# LPRD_Sensors_1_4.net
KiCad netlist of a schematic drawn in EAGLE
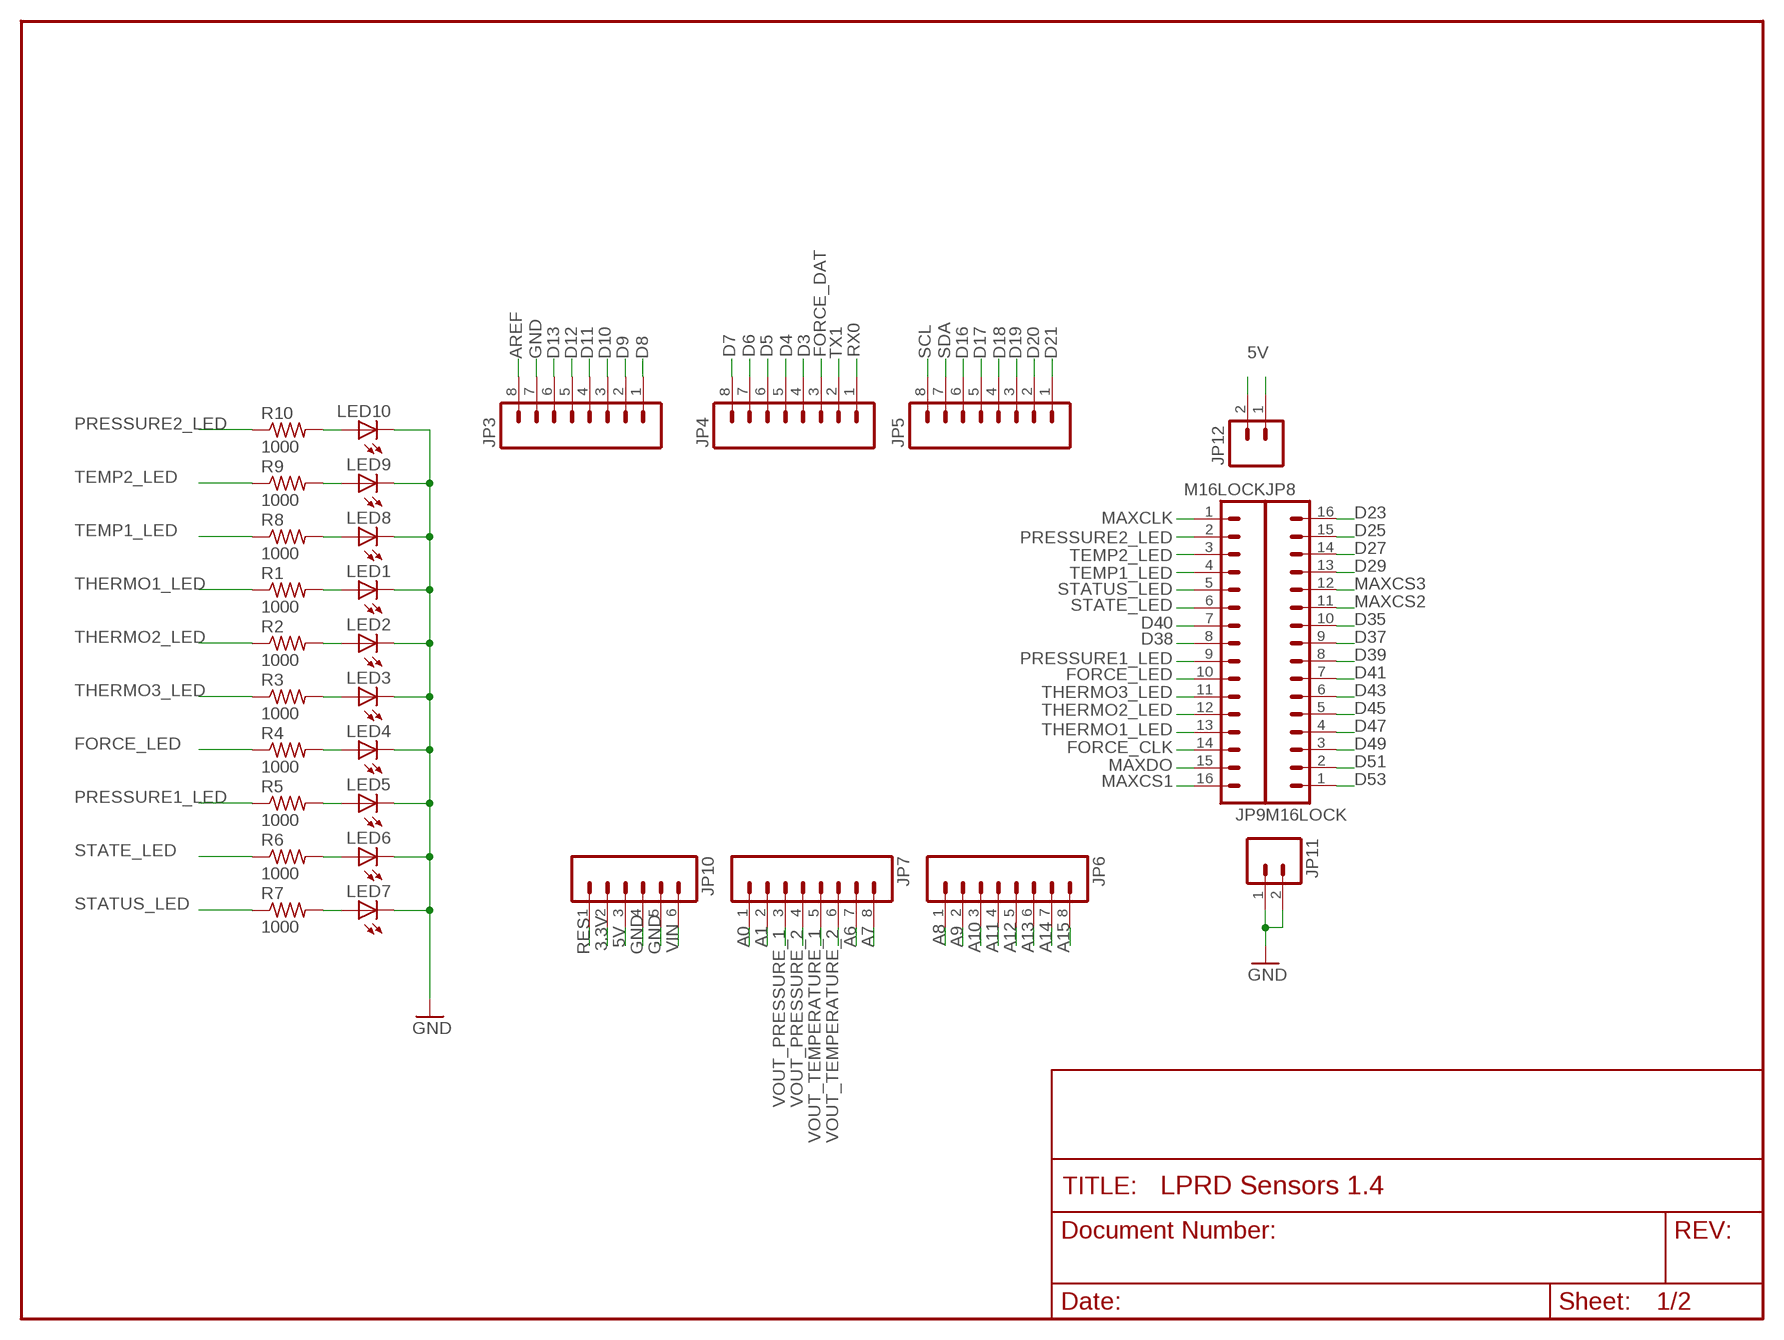
[diagram p0: schematic, sheet 1]
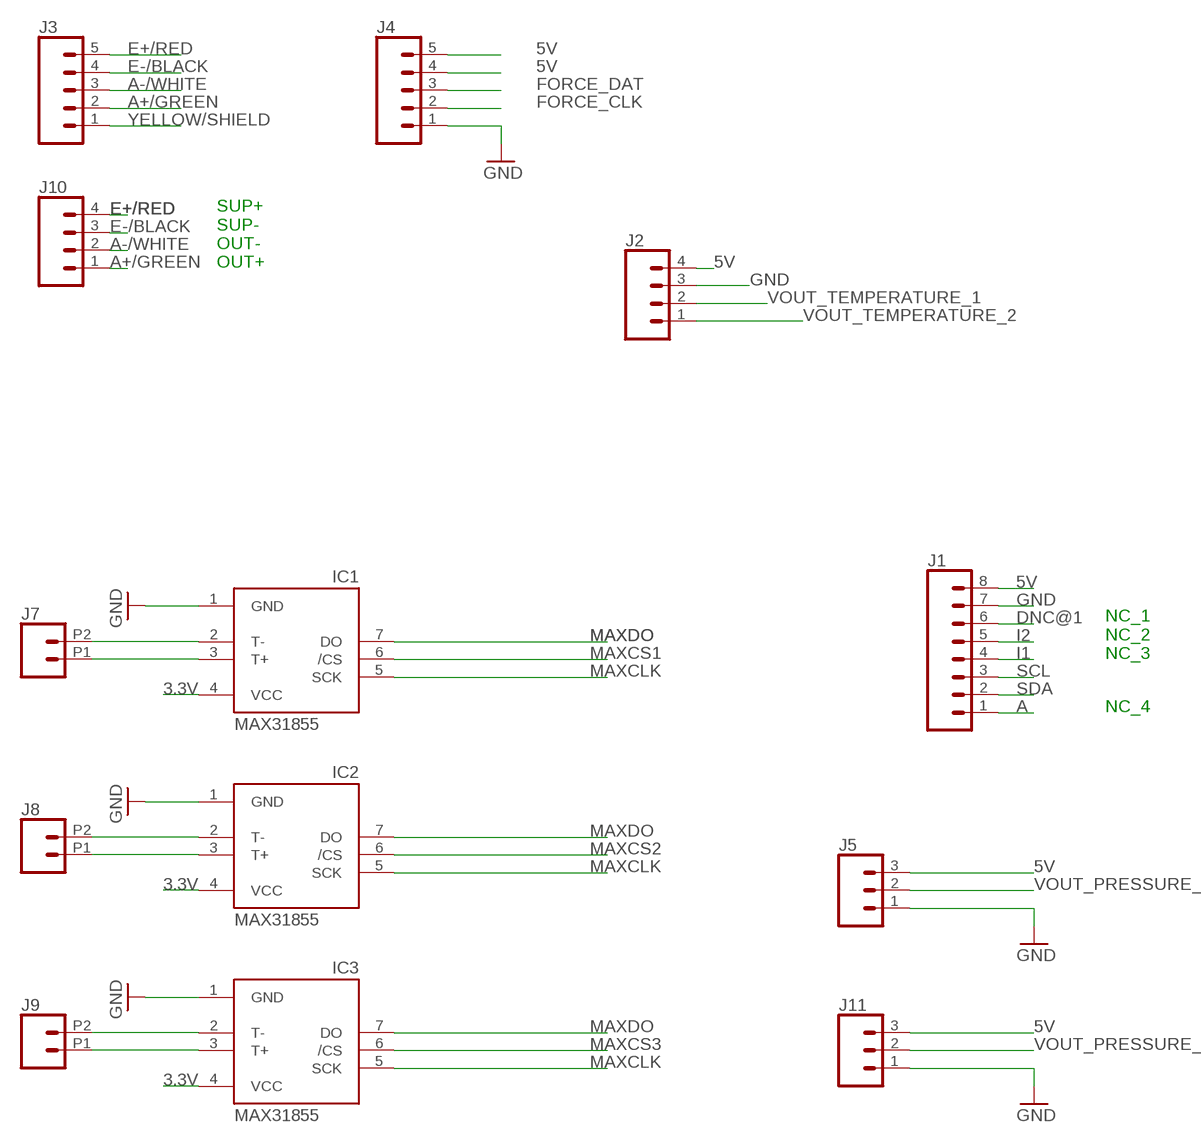
[diagram p1: schematic, sheet 2]

(export (version "E")
  (design (tool "Eeschema 10.0.6"))
  (components
    (comp (ref "IC1")
      (value "MAX31855")
      (footprint "eagle-import:SO08")
      (libsource (lib "eagle-import") (part "MAX6675"))
    )
    (comp (ref "IC2")
      (value "MAX31855")
      (footprint "eagle-import:SO08")
      (libsource (lib "eagle-import") (part "MAX6675"))
    )
    (comp (ref "IC3")
      (value "MAX31855")
      (footprint "eagle-import:SO08")
      (libsource (lib "eagle-import") (part "MAX6675"))
    )
    (comp (ref "J1")
      (value "CONN_08\"")
      (footprint "eagle-import:1X08")
      (libsource (lib "eagle-import") (part "CONN_08{dblquote}"))
    )
    (comp (ref "J2")
      (value "CONN_04")
      (footprint "eagle-import:1X04")
      (libsource (lib "eagle-import") (part "CONN_04"))
    )
    (comp (ref "J3")
      (value "CONN_05")
      (footprint "eagle-import:1X05")
      (libsource (lib "eagle-import") (part "CONN_05"))
    )
    (comp (ref "J4")
      (value "CONN_05")
      (footprint "eagle-import:1X05")
      (libsource (lib "eagle-import") (part "CONN_05"))
    )
    (comp (ref "J5")
      (value "CONN_03-SCREW-5MM")
      (footprint "eagle-import:SCREWTERMINAL-5MM-3")
      (libsource (lib "eagle-import") (part "CONN_03-SCREW-5MM"))
    )
    (comp (ref "J7")
      (value "CONN_022.54MM_SCREWTERM")
      (footprint "eagle-import:1X02_2.54_SCREWTERM")
      (libsource (lib "eagle-import") (part "CONN_022.54MM_SCREWTERM"))
    )
    (comp (ref "J8")
      (value "CONN_022.54MM_SCREWTERM")
      (footprint "eagle-import:1X02_2.54_SCREWTERM")
      (libsource (lib "eagle-import") (part "CONN_022.54MM_SCREWTERM"))
    )
    (comp (ref "J9")
      (value "CONN_022.54MM_SCREWTERM")
      (footprint "eagle-import:1X02_2.54_SCREWTERM")
      (libsource (lib "eagle-import") (part "CONN_022.54MM_SCREWTERM"))
    )
    (comp (ref "J10")
      (value "CONN_04SCREW")
      (footprint "eagle-import:SCREWTERMINAL-3.5MM-4")
      (libsource (lib "eagle-import") (part "CONN_04SCREW"))
    )
    (comp (ref "J11")
      (value "CONN_03-SCREW-5MM")
      (footprint "eagle-import:SCREWTERMINAL-5MM-3")
      (libsource (lib "eagle-import") (part "CONN_03-SCREW-5MM"))
    )
    (comp (ref "JP3")
      (value "M08LOCK")
      (footprint "eagle-import:1X08_LOCK")
      (libsource (lib "eagle-import") (part "M08LOCK"))
    )
    (comp (ref "JP4")
      (value "M08LOCK")
      (footprint "eagle-import:1X08_LOCK")
      (libsource (lib "eagle-import") (part "M08LOCK"))
    )
    (comp (ref "JP5")
      (value "M08LOCK")
      (footprint "eagle-import:1X08_LOCK")
      (libsource (lib "eagle-import") (part "M08LOCK"))
    )
    (comp (ref "JP6")
      (value "M08LOCK")
      (footprint "eagle-import:1X08_LOCK")
      (libsource (lib "eagle-import") (part "M08LOCK"))
    )
    (comp (ref "JP7")
      (value "M08LOCK")
      (footprint "eagle-import:1X08_LOCK")
      (libsource (lib "eagle-import") (part "M08LOCK"))
    )
    (comp (ref "JP8")
      (value "M16LOCK")
      (footprint "eagle-import:1X16_LOCK")
      (libsource (lib "eagle-import") (part "M16LOCK"))
    )
    (comp (ref "JP9")
      (value "M16LOCK")
      (footprint "eagle-import:1X16_LOCK")
      (libsource (lib "eagle-import") (part "M16LOCK"))
    )
    (comp (ref "JP10")
      (value "M06LOCK")
      (footprint "eagle-import:1X06_LOCK")
      (libsource (lib "eagle-import") (part "M06LOCK"))
    )
    (comp (ref "JP11")
      (value "M02LOCK")
      (footprint "eagle-import:1X02_LOCK")
      (libsource (lib "eagle-import") (part "M02LOCK"))
    )
    (comp (ref "JP12")
      (value "M02LOCK")
      (footprint "eagle-import:1X02_LOCK")
      (libsource (lib "eagle-import") (part "M02LOCK"))
    )
    (comp (ref "LED1")
      (value "LEDCHIP-LED0805")
      (footprint "eagle-import:CHIP-LED0805")
      (libsource (lib "eagle-import") (part "LEDCHIP-LED0805"))
    )
    (comp (ref "LED2")
      (value "LEDCHIP-LED0805")
      (footprint "eagle-import:CHIP-LED0805")
      (libsource (lib "eagle-import") (part "LEDCHIP-LED0805"))
    )
    (comp (ref "LED3")
      (value "LEDCHIP-LED0805")
      (footprint "eagle-import:CHIP-LED0805")
      (libsource (lib "eagle-import") (part "LEDCHIP-LED0805"))
    )
    (comp (ref "LED4")
      (value "LEDCHIP-LED0805")
      (footprint "eagle-import:CHIP-LED0805")
      (libsource (lib "eagle-import") (part "LEDCHIP-LED0805"))
    )
    (comp (ref "LED5")
      (value "LEDCHIP-LED0805")
      (footprint "eagle-import:CHIP-LED0805")
      (libsource (lib "eagle-import") (part "LEDCHIP-LED0805"))
    )
    (comp (ref "LED6")
      (value "LEDCHIP-LED0805")
      (footprint "eagle-import:CHIP-LED0805")
      (libsource (lib "eagle-import") (part "LEDCHIP-LED0805"))
    )
    (comp (ref "LED7")
      (value "LEDCHIP-LED0805")
      (footprint "eagle-import:CHIP-LED0805")
      (libsource (lib "eagle-import") (part "LEDCHIP-LED0805"))
    )
    (comp (ref "LED8")
      (value "LEDCHIP-LED0805")
      (footprint "eagle-import:CHIP-LED0805")
      (libsource (lib "eagle-import") (part "LEDCHIP-LED0805"))
    )
    (comp (ref "LED9")
      (value "LEDCHIP-LED0805")
      (footprint "eagle-import:CHIP-LED0805")
      (libsource (lib "eagle-import") (part "LEDCHIP-LED0805"))
    )
    (comp (ref "LED10")
      (value "LEDCHIP-LED0805")
      (footprint "eagle-import:CHIP-LED0805")
      (libsource (lib "eagle-import") (part "LEDCHIP-LED0805"))
    )
    (comp (ref "R1")
      (value "1000")
      (footprint "eagle-import:R0805")
      (libsource (lib "eagle-import") (part "R-US_R0805"))
    )
    (comp (ref "R2")
      (value "1000")
      (footprint "eagle-import:R0805")
      (libsource (lib "eagle-import") (part "R-US_R0805"))
    )
    (comp (ref "R3")
      (value "1000")
      (footprint "eagle-import:R0805")
      (libsource (lib "eagle-import") (part "R-US_R0805"))
    )
    (comp (ref "R4")
      (value "1000")
      (footprint "eagle-import:R0805")
      (libsource (lib "eagle-import") (part "R-US_R0805"))
    )
    (comp (ref "R5")
      (value "1000")
      (footprint "eagle-import:R0805")
      (libsource (lib "eagle-import") (part "R-US_R0805"))
    )
    (comp (ref "R6")
      (value "1000")
      (footprint "eagle-import:R0805")
      (libsource (lib "eagle-import") (part "R-US_R0805"))
    )
    (comp (ref "R7")
      (value "1000")
      (footprint "eagle-import:R0805")
      (libsource (lib "eagle-import") (part "R-US_R0805"))
    )
    (comp (ref "R8")
      (value "1000")
      (footprint "eagle-import:R0805")
      (libsource (lib "eagle-import") (part "R-US_R0805"))
    )
    (comp (ref "R9")
      (value "1000")
      (footprint "eagle-import:R0805")
      (libsource (lib "eagle-import") (part "R-US_R0805"))
    )
    (comp (ref "R10")
      (value "1000")
      (footprint "eagle-import:R0805")
      (libsource (lib "eagle-import") (part "R-US_R0805"))
    )
  )
  (nets
    (net (code "1") (name "3.3V") (class "Default")
      (node (ref "IC1") (pin "4") (pinfunction "VCC_4") (pintype "power_in"))
      (node (ref "IC2") (pin "4") (pinfunction "VCC_4") (pintype "power_in"))
      (node (ref "IC3") (pin "4") (pinfunction "VCC_4") (pintype "power_in"))
      (node (ref "JP10") (pin "2") (pinfunction "2_2") (pintype "passive"))
    )
    (net (code "2") (name "5V") (class "Default")
      (node (ref "J1") (pin "8") (pinfunction "8_8") (pintype "passive"))
      (node (ref "J11") (pin "3") (pinfunction "3_3") (pintype "passive"))
      (node (ref "J2") (pin "4") (pinfunction "4_4") (pintype "passive"))
      (node (ref "J4") (pin "4") (pinfunction "4_4") (pintype "passive"))
      (node (ref "J4") (pin "5") (pinfunction "5_5") (pintype "passive"))
      (node (ref "J5") (pin "3") (pinfunction "3_3") (pintype "passive"))
      (node (ref "JP10") (pin "3") (pinfunction "3_3") (pintype "passive"))
      (node (ref "JP12") (pin "1") (pinfunction "1_1") (pintype "passive"))
      (node (ref "JP12") (pin "2") (pinfunction "2_2") (pintype "passive"))
    )
    (net (code "3") (name "A") (class "Default")
      (node (ref "J1") (pin "1") (pinfunction "1_1") (pintype "passive"))
    )
    (net (code "4") (name "A+{slash}GREEN") (class "Default")
      (node (ref "J10") (pin "1") (pinfunction "1_1") (pintype "passive"))
      (node (ref "J3") (pin "2") (pinfunction "2_2") (pintype "passive"))
    )
    (net (code "5") (name "A-{slash}WHITE") (class "Default")
      (node (ref "J10") (pin "2") (pinfunction "2_2") (pintype "passive"))
      (node (ref "J3") (pin "3") (pinfunction "3_3") (pintype "passive"))
    )
    (net (code "6") (name "A0") (class "Default")
      (node (ref "JP7") (pin "1") (pinfunction "1_1") (pintype "passive"))
    )
    (net (code "7") (name "A1") (class "Default")
      (node (ref "JP7") (pin "2") (pinfunction "2_2") (pintype "passive"))
    )
    (net (code "8") (name "A6") (class "Default")
      (node (ref "JP7") (pin "7") (pinfunction "7_7") (pintype "passive"))
    )
    (net (code "9") (name "A7") (class "Default")
      (node (ref "JP7") (pin "8") (pinfunction "8_8") (pintype "passive"))
    )
    (net (code "10") (name "A8") (class "Default")
      (node (ref "JP6") (pin "1") (pinfunction "1_1") (pintype "passive"))
    )
    (net (code "11") (name "A9") (class "Default")
      (node (ref "JP6") (pin "2") (pinfunction "2_2") (pintype "passive"))
    )
    (net (code "12") (name "A10") (class "Default")
      (node (ref "JP6") (pin "3") (pinfunction "3_3") (pintype "passive"))
    )
    (net (code "13") (name "A11") (class "Default")
      (node (ref "JP6") (pin "4") (pinfunction "4_4") (pintype "passive"))
    )
    (net (code "14") (name "A12") (class "Default")
      (node (ref "JP6") (pin "5") (pinfunction "5_5") (pintype "passive"))
    )
    (net (code "15") (name "A13") (class "Default")
      (node (ref "JP6") (pin "6") (pinfunction "6_6") (pintype "passive"))
    )
    (net (code "16") (name "A14") (class "Default")
      (node (ref "JP6") (pin "7") (pinfunction "7_7") (pintype "passive"))
    )
    (net (code "17") (name "A15") (class "Default")
      (node (ref "JP6") (pin "8") (pinfunction "8_8") (pintype "passive"))
    )
    (net (code "18") (name "AREF") (class "Default")
      (node (ref "JP3") (pin "8") (pinfunction "8_8") (pintype "passive"))
    )
    (net (code "19") (name "D3") (class "Default")
      (node (ref "JP4") (pin "4") (pinfunction "4_4") (pintype "passive"))
    )
    (net (code "20") (name "D4") (class "Default")
      (node (ref "JP4") (pin "5") (pinfunction "5_5") (pintype "passive"))
    )
    (net (code "21") (name "D5") (class "Default")
      (node (ref "JP4") (pin "6") (pinfunction "6_6") (pintype "passive"))
    )
    (net (code "22") (name "D6") (class "Default")
      (node (ref "JP4") (pin "7") (pinfunction "7_7") (pintype "passive"))
    )
    (net (code "23") (name "D7") (class "Default")
      (node (ref "JP4") (pin "8") (pinfunction "8_8") (pintype "passive"))
    )
    (net (code "24") (name "D8") (class "Default")
      (node (ref "JP3") (pin "1") (pinfunction "1_1") (pintype "passive"))
    )
    (net (code "25") (name "D9") (class "Default")
      (node (ref "JP3") (pin "2") (pinfunction "2_2") (pintype "passive"))
    )
    (net (code "26") (name "D10") (class "Default")
      (node (ref "JP3") (pin "3") (pinfunction "3_3") (pintype "passive"))
    )
    (net (code "27") (name "D11") (class "Default")
      (node (ref "JP3") (pin "4") (pinfunction "4_4") (pintype "passive"))
    )
    (net (code "28") (name "D12") (class "Default")
      (node (ref "JP3") (pin "5") (pinfunction "5_5") (pintype "passive"))
    )
    (net (code "29") (name "D13") (class "Default")
      (node (ref "JP3") (pin "6") (pinfunction "6_6") (pintype "passive"))
    )
    (net (code "30") (name "D16") (class "Default")
      (node (ref "JP5") (pin "6") (pinfunction "6_6") (pintype "passive"))
    )
    (net (code "31") (name "D17") (class "Default")
      (node (ref "JP5") (pin "5") (pinfunction "5_5") (pintype "passive"))
    )
    (net (code "32") (name "D18") (class "Default")
      (node (ref "JP5") (pin "4") (pinfunction "4_4") (pintype "passive"))
    )
    (net (code "33") (name "D19") (class "Default")
      (node (ref "JP5") (pin "3") (pinfunction "3_3") (pintype "passive"))
    )
    (net (code "34") (name "D20") (class "Default")
      (node (ref "JP5") (pin "2") (pinfunction "2_2") (pintype "passive"))
    )
    (net (code "35") (name "D21") (class "Default")
      (node (ref "JP5") (pin "1") (pinfunction "1_1") (pintype "passive"))
    )
    (net (code "36") (name "D23") (class "Default")
      (node (ref "JP8") (pin "16") (pinfunction "16_16") (pintype "passive"))
    )
    (net (code "37") (name "D25") (class "Default")
      (node (ref "JP8") (pin "15") (pinfunction "15_15") (pintype "passive"))
    )
    (net (code "38") (name "D27") (class "Default")
      (node (ref "JP8") (pin "14") (pinfunction "14_14") (pintype "passive"))
    )
    (net (code "39") (name "D29") (class "Default")
      (node (ref "JP8") (pin "13") (pinfunction "13_13") (pintype "passive"))
    )
    (net (code "40") (name "D35") (class "Default")
      (node (ref "JP8") (pin "10") (pinfunction "10_10") (pintype "passive"))
    )
    (net (code "41") (name "D37") (class "Default")
      (node (ref "JP8") (pin "9") (pinfunction "9_9") (pintype "passive"))
    )
    (net (code "42") (name "D38") (class "Default")
      (node (ref "JP9") (pin "8") (pinfunction "8_8") (pintype "passive"))
    )
    (net (code "43") (name "D39") (class "Default")
      (node (ref "JP8") (pin "8") (pinfunction "8_8") (pintype "passive"))
    )
    (net (code "44") (name "D40") (class "Default")
      (node (ref "JP9") (pin "7") (pinfunction "7_7") (pintype "passive"))
    )
    (net (code "45") (name "D41") (class "Default")
      (node (ref "JP8") (pin "7") (pinfunction "7_7") (pintype "passive"))
    )
    (net (code "46") (name "D43") (class "Default")
      (node (ref "JP8") (pin "6") (pinfunction "6_6") (pintype "passive"))
    )
    (net (code "47") (name "D45") (class "Default")
      (node (ref "JP8") (pin "5") (pinfunction "5_5") (pintype "passive"))
    )
    (net (code "48") (name "D47") (class "Default")
      (node (ref "JP8") (pin "4") (pinfunction "4_4") (pintype "passive"))
    )
    (net (code "49") (name "D49") (class "Default")
      (node (ref "JP8") (pin "3") (pinfunction "3_3") (pintype "passive"))
    )
    (net (code "50") (name "D51") (class "Default")
      (node (ref "JP8") (pin "2") (pinfunction "2_2") (pintype "passive"))
    )
    (net (code "51") (name "D53") (class "Default")
      (node (ref "JP8") (pin "1") (pinfunction "1_1") (pintype "passive"))
    )
    (net (code "52") (name "DNC@1") (class "Default")
      (node (ref "J1") (pin "6") (pinfunction "6_6") (pintype "passive"))
    )
    (net (code "53") (name "E+{slash}RED") (class "Default")
      (node (ref "J10") (pin "4") (pinfunction "4_4") (pintype "passive"))
      (node (ref "J3") (pin "5") (pinfunction "5_5") (pintype "passive"))
    )
    (net (code "54") (name "E-{slash}BLACK") (class "Default")
      (node (ref "J10") (pin "3") (pinfunction "3_3") (pintype "passive"))
      (node (ref "J3") (pin "4") (pinfunction "4_4") (pintype "passive"))
    )
    (net (code "55") (name "FORCE_CLK") (class "Default")
      (node (ref "J4") (pin "2") (pinfunction "2_2") (pintype "passive"))
      (node (ref "JP9") (pin "14") (pinfunction "14_14") (pintype "passive"))
    )
    (net (code "56") (name "FORCE_DAT") (class "Default")
      (node (ref "J4") (pin "3") (pinfunction "3_3") (pintype "passive"))
      (node (ref "JP4") (pin "3") (pinfunction "3_3") (pintype "passive"))
    )
    (net (code "57") (name "FORCE_LED") (class "Default")
      (node (ref "JP9") (pin "10") (pinfunction "10_10") (pintype "passive"))
      (node (ref "R4") (pin "1") (pinfunction "1_1") (pintype "passive"))
    )
    (net (code "58") (name "GND") (class "Default")
      (node (ref "IC1") (pin "1") (pinfunction "GND_1") (pintype "power_in"))
      (node (ref "IC2") (pin "1") (pinfunction "GND_1") (pintype "power_in"))
      (node (ref "IC3") (pin "1") (pinfunction "GND_1") (pintype "power_in"))
      (node (ref "J1") (pin "7") (pinfunction "7_7") (pintype "passive"))
      (node (ref "J11") (pin "1") (pinfunction "1_1") (pintype "passive"))
      (node (ref "J2") (pin "3") (pinfunction "3_3") (pintype "passive"))
      (node (ref "J4") (pin "1") (pinfunction "1_1") (pintype "passive"))
      (node (ref "J5") (pin "1") (pinfunction "1_1") (pintype "passive"))
      (node (ref "JP10") (pin "4") (pinfunction "4_4") (pintype "passive"))
      (node (ref "JP10") (pin "5") (pinfunction "5_5") (pintype "passive"))
      (node (ref "JP11") (pin "1") (pinfunction "1_1") (pintype "passive"))
      (node (ref "JP11") (pin "2") (pinfunction "2_2") (pintype "passive"))
      (node (ref "JP3") (pin "7") (pinfunction "7_7") (pintype "passive"))
      (node (ref "LED1") (pin "C") (pinfunction "C_C") (pintype "passive"))
      (node (ref "LED10") (pin "C") (pinfunction "C_C") (pintype "passive"))
      (node (ref "LED2") (pin "C") (pinfunction "C_C") (pintype "passive"))
      (node (ref "LED3") (pin "C") (pinfunction "C_C") (pintype "passive"))
      (node (ref "LED4") (pin "C") (pinfunction "C_C") (pintype "passive"))
      (node (ref "LED5") (pin "C") (pinfunction "C_C") (pintype "passive"))
      (node (ref "LED6") (pin "C") (pinfunction "C_C") (pintype "passive"))
      (node (ref "LED7") (pin "C") (pinfunction "C_C") (pintype "passive"))
      (node (ref "LED8") (pin "C") (pinfunction "C_C") (pintype "passive"))
      (node (ref "LED9") (pin "C") (pinfunction "C_C") (pintype "passive"))
    )
    (net (code "59") (name "I1") (class "Default")
      (node (ref "J1") (pin "4") (pinfunction "4_4") (pintype "passive"))
    )
    (net (code "60") (name "I2") (class "Default")
      (node (ref "J1") (pin "5") (pinfunction "5_5") (pintype "passive"))
    )
    (net (code "61") (name "MAXCLK") (class "Default")
      (node (ref "IC1") (pin "5") (pinfunction "SCK_5") (pintype "input"))
      (node (ref "IC2") (pin "5") (pinfunction "SCK_5") (pintype "input"))
      (node (ref "IC3") (pin "5") (pinfunction "SCK_5") (pintype "input"))
      (node (ref "JP9") (pin "1") (pinfunction "1_1") (pintype "passive"))
    )
    (net (code "62") (name "MAXCS1") (class "Default")
      (node (ref "IC1") (pin "6") (pinfunction "/CS_6") (pintype "input"))
      (node (ref "JP9") (pin "16") (pinfunction "16_16") (pintype "passive"))
    )
    (net (code "63") (name "MAXCS2") (class "Default")
      (node (ref "IC2") (pin "6") (pinfunction "/CS_6") (pintype "input"))
      (node (ref "JP8") (pin "11") (pinfunction "11_11") (pintype "passive"))
    )
    (net (code "64") (name "MAXCS3") (class "Default")
      (node (ref "IC3") (pin "6") (pinfunction "/CS_6") (pintype "input"))
      (node (ref "JP8") (pin "12") (pinfunction "12_12") (pintype "passive"))
    )
    (net (code "65") (name "MAXDO") (class "Default")
      (node (ref "IC1") (pin "7") (pinfunction "DO_7") (pintype "output"))
      (node (ref "IC2") (pin "7") (pinfunction "DO_7") (pintype "output"))
      (node (ref "IC3") (pin "7") (pinfunction "DO_7") (pintype "output"))
      (node (ref "JP9") (pin "15") (pinfunction "15_15") (pintype "passive"))
    )
    (net (code "66") (name "Net-(IC1-T+)") (class "Default")
      (node (ref "IC1") (pin "3") (pinfunction "T+_3") (pintype "input"))
      (node (ref "J7") (pin "P1") (pinfunction "1_P1") (pintype "passive"))
    )
    (net (code "67") (name "Net-(IC1-T-)") (class "Default")
      (node (ref "IC1") (pin "2") (pinfunction "T-_2") (pintype "input"))
      (node (ref "J7") (pin "P2") (pinfunction "2_P2") (pintype "passive"))
    )
    (net (code "68") (name "Net-(IC2-T+)") (class "Default")
      (node (ref "IC2") (pin "3") (pinfunction "T+_3") (pintype "input"))
      (node (ref "J8") (pin "P1") (pinfunction "1_P1") (pintype "passive"))
    )
    (net (code "69") (name "Net-(IC2-T-)") (class "Default")
      (node (ref "IC2") (pin "2") (pinfunction "T-_2") (pintype "input"))
      (node (ref "J8") (pin "P2") (pinfunction "2_P2") (pintype "passive"))
    )
    (net (code "70") (name "Net-(IC3-T+)") (class "Default")
      (node (ref "IC3") (pin "3") (pinfunction "T+_3") (pintype "input"))
      (node (ref "J9") (pin "P1") (pinfunction "1_P1") (pintype "passive"))
    )
    (net (code "71") (name "Net-(IC3-T-)") (class "Default")
      (node (ref "IC3") (pin "2") (pinfunction "T-_2") (pintype "input"))
      (node (ref "J9") (pin "P2") (pinfunction "2_P2") (pintype "passive"))
    )
    (net (code "72") (name "Net-(LED1-PadA)") (class "Default")
      (node (ref "LED1") (pin "A") (pinfunction "A_A") (pintype "passive"))
      (node (ref "R1") (pin "2") (pinfunction "2_2") (pintype "passive"))
    )
    (net (code "73") (name "Net-(LED2-PadA)") (class "Default")
      (node (ref "LED2") (pin "A") (pinfunction "A_A") (pintype "passive"))
      (node (ref "R2") (pin "2") (pinfunction "2_2") (pintype "passive"))
    )
    (net (code "74") (name "Net-(LED3-PadA)") (class "Default")
      (node (ref "LED3") (pin "A") (pinfunction "A_A") (pintype "passive"))
      (node (ref "R3") (pin "2") (pinfunction "2_2") (pintype "passive"))
    )
    (net (code "75") (name "Net-(LED4-PadA)") (class "Default")
      (node (ref "LED4") (pin "A") (pinfunction "A_A") (pintype "passive"))
      (node (ref "R4") (pin "2") (pinfunction "2_2") (pintype "passive"))
    )
    (net (code "76") (name "Net-(LED5-PadA)") (class "Default")
      (node (ref "LED5") (pin "A") (pinfunction "A_A") (pintype "passive"))
      (node (ref "R5") (pin "2") (pinfunction "2_2") (pintype "passive"))
    )
    (net (code "77") (name "Net-(LED6-PadA)") (class "Default")
      (node (ref "LED6") (pin "A") (pinfunction "A_A") (pintype "passive"))
      (node (ref "R6") (pin "2") (pinfunction "2_2") (pintype "passive"))
    )
    (net (code "78") (name "Net-(LED7-PadA)") (class "Default")
      (node (ref "LED7") (pin "A") (pinfunction "A_A") (pintype "passive"))
      (node (ref "R7") (pin "2") (pinfunction "2_2") (pintype "passive"))
    )
    (net (code "79") (name "Net-(LED8-PadA)") (class "Default")
      (node (ref "LED8") (pin "A") (pinfunction "A_A") (pintype "passive"))
      (node (ref "R8") (pin "2") (pinfunction "2_2") (pintype "passive"))
    )
    (net (code "80") (name "Net-(LED9-PadA)") (class "Default")
      (node (ref "LED9") (pin "A") (pinfunction "A_A") (pintype "passive"))
      (node (ref "R9") (pin "2") (pinfunction "2_2") (pintype "passive"))
    )
    (net (code "81") (name "Net-(LED10-PadA)") (class "Default")
      (node (ref "LED10") (pin "A") (pinfunction "A_A") (pintype "passive"))
      (node (ref "R10") (pin "2") (pinfunction "2_2") (pintype "passive"))
    )
    (net (code "82") (name "PRESSURE1_LED") (class "Default")
      (node (ref "JP9") (pin "9") (pinfunction "9_9") (pintype "passive"))
      (node (ref "R5") (pin "1") (pinfunction "1_1") (pintype "passive"))
    )
    (net (code "83") (name "PRESSURE2_LED") (class "Default")
      (node (ref "JP9") (pin "2") (pinfunction "2_2") (pintype "passive"))
      (node (ref "R10") (pin "1") (pinfunction "1_1") (pintype "passive"))
    )
    (net (code "84") (name "RES") (class "Default")
      (node (ref "JP10") (pin "1") (pinfunction "1_1") (pintype "passive"))
    )
    (net (code "85") (name "RX0") (class "Default")
      (node (ref "JP4") (pin "1") (pinfunction "1_1") (pintype "passive"))
    )
    (net (code "86") (name "SCL") (class "Default")
      (node (ref "J1") (pin "3") (pinfunction "3_3") (pintype "passive"))
      (node (ref "JP5") (pin "8") (pinfunction "8_8") (pintype "passive"))
    )
    (net (code "87") (name "SDA") (class "Default")
      (node (ref "J1") (pin "2") (pinfunction "2_2") (pintype "passive"))
      (node (ref "JP5") (pin "7") (pinfunction "7_7") (pintype "passive"))
    )
    (net (code "88") (name "STATE_LED") (class "Default")
      (node (ref "JP9") (pin "6") (pinfunction "6_6") (pintype "passive"))
      (node (ref "R6") (pin "1") (pinfunction "1_1") (pintype "passive"))
    )
    (net (code "89") (name "STATUS_LED") (class "Default")
      (node (ref "JP9") (pin "5") (pinfunction "5_5") (pintype "passive"))
      (node (ref "R7") (pin "1") (pinfunction "1_1") (pintype "passive"))
    )
    (net (code "90") (name "TEMP1_LED") (class "Default")
      (node (ref "JP9") (pin "4") (pinfunction "4_4") (pintype "passive"))
      (node (ref "R8") (pin "1") (pinfunction "1_1") (pintype "passive"))
    )
    (net (code "91") (name "TEMP2_LED") (class "Default")
      (node (ref "JP9") (pin "3") (pinfunction "3_3") (pintype "passive"))
      (node (ref "R9") (pin "1") (pinfunction "1_1") (pintype "passive"))
    )
    (net (code "92") (name "THERMO1_LED") (class "Default")
      (node (ref "JP9") (pin "13") (pinfunction "13_13") (pintype "passive"))
      (node (ref "R1") (pin "1") (pinfunction "1_1") (pintype "passive"))
    )
    (net (code "93") (name "THERMO2_LED") (class "Default")
      (node (ref "JP9") (pin "12") (pinfunction "12_12") (pintype "passive"))
      (node (ref "R2") (pin "1") (pinfunction "1_1") (pintype "passive"))
    )
    (net (code "94") (name "THERMO3_LED") (class "Default")
      (node (ref "JP9") (pin "11") (pinfunction "11_11") (pintype "passive"))
      (node (ref "R3") (pin "1") (pinfunction "1_1") (pintype "passive"))
    )
    (net (code "95") (name "TX1") (class "Default")
      (node (ref "JP4") (pin "2") (pinfunction "2_2") (pintype "passive"))
    )
    (net (code "96") (name "VIN") (class "Default")
      (node (ref "JP10") (pin "6") (pinfunction "6_6") (pintype "passive"))
    )
    (net (code "97") (name "VOUT_PRESSURE_1") (class "Default")
      (node (ref "J5") (pin "2") (pinfunction "2_2") (pintype "passive"))
      (node (ref "JP7") (pin "3") (pinfunction "3_3") (pintype "passive"))
    )
    (net (code "98") (name "VOUT_PRESSURE_2") (class "Default")
      (node (ref "J11") (pin "2") (pinfunction "2_2") (pintype "passive"))
      (node (ref "JP7") (pin "4") (pinfunction "4_4") (pintype "passive"))
    )
    (net (code "99") (name "VOUT_TEMPERATURE_1") (class "Default")
      (node (ref "J2") (pin "2") (pinfunction "2_2") (pintype "passive"))
      (node (ref "JP7") (pin "5") (pinfunction "5_5") (pintype "passive"))
    )
    (net (code "100") (name "VOUT_TEMPERATURE_2") (class "Default")
      (node (ref "J2") (pin "1") (pinfunction "1_1") (pintype "passive"))
      (node (ref "JP7") (pin "6") (pinfunction "6_6") (pintype "passive"))
    )
    (net (code "101") (name "YELLOW{slash}SHIELD") (class "Default")
      (node (ref "J3") (pin "1") (pinfunction "1_1") (pintype "passive"))
    )
  )
)
